# Microcontroller.net
KiCad netlist of a schematic drawn in Altium Designer
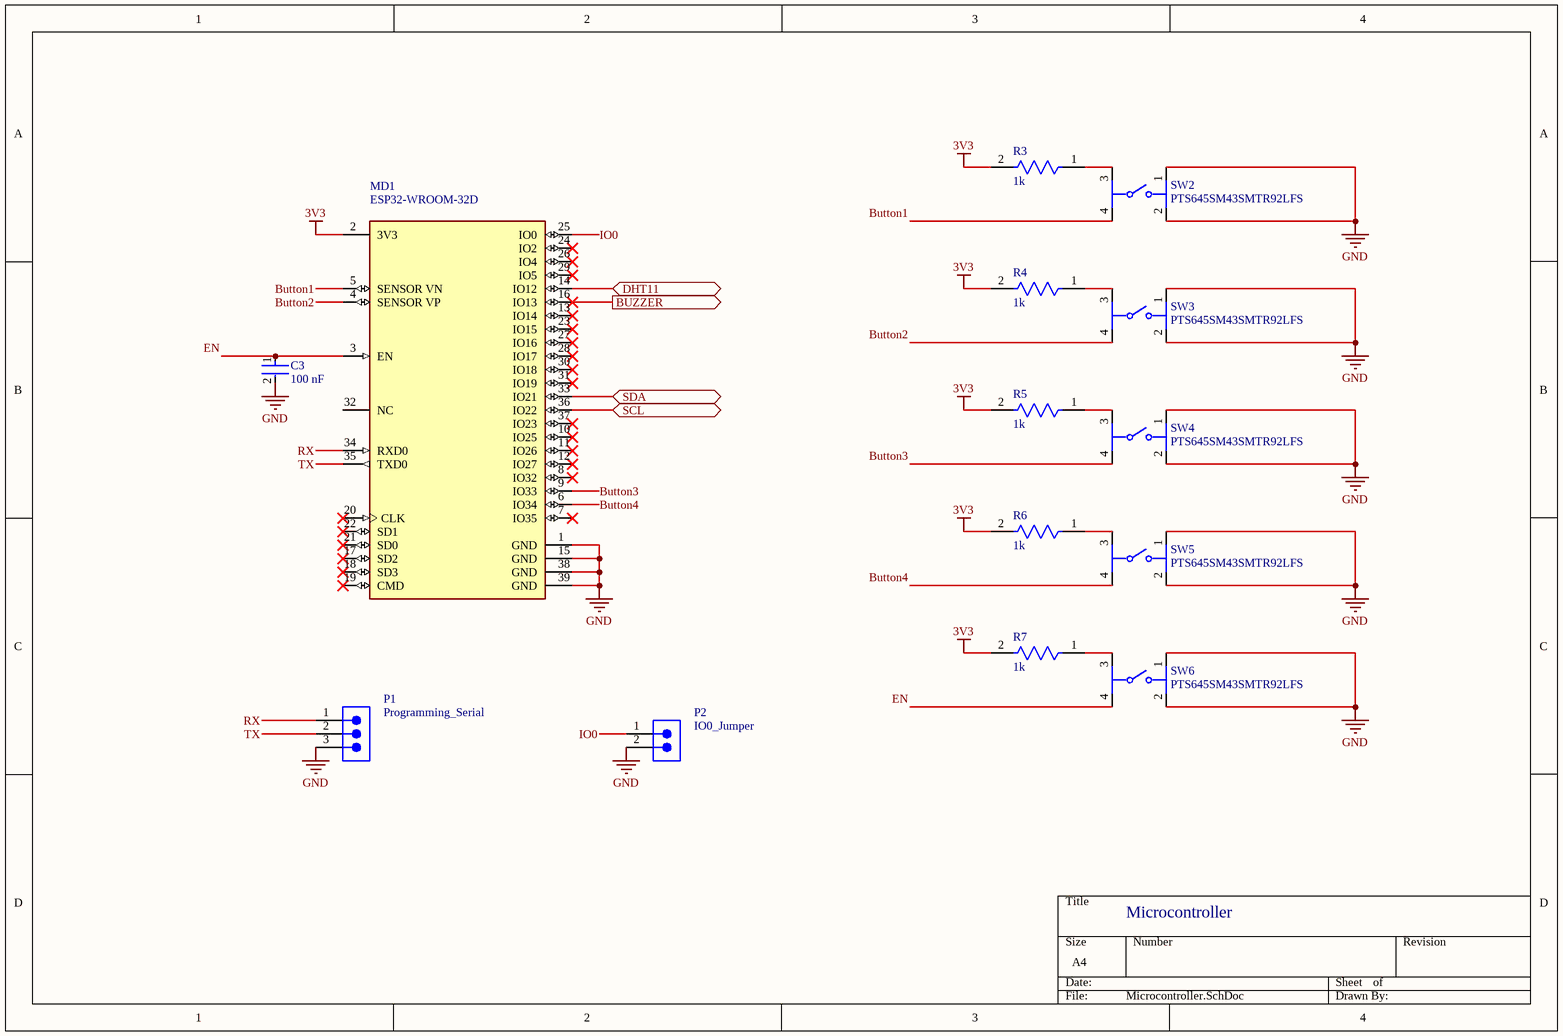
[diagram p0: Microcontroller.SchDoc]

(export (version "E")
  (design (tool "Eeschema 10.0.6"))
  (components
    (comp (ref "C3")
      (value "100 nF")
      (footprint "FP-CC1206-1_25-MFG")
      (description "CAP CER 0.1UF 50V X7R 1206")
      (fields
        (field (name "OCTOPART") "https://octopart.com/cc1206krx7r9bb104-yageo-39467816")
        (field (name "TOLERANCE") "0.1")
      )
      (libsource (lib "Altium Content Vault") (part "11868f565c42a9108669ba33697ecf6"))
    )
    (comp (ref "MD1")
      (value "ESP32-WROOM-32D")
      (footprint "FP-ESP32-WROOM-32D-MFG")
      (description "WIFI MODULE 32MBITS SPI FLASH")
      (fields
        (field (name "OCTOPART") "https://octopart.com/esp32-wroom-32d-espressif+systems-91040050")
        (field (name "MANUFACTURER") "Espressif Systems")
      )
      (libsource (lib "Altium Content Vault") (part "a031a76f8c27026a7a7f4657ff233a3"))
    )
    (comp (ref "P1")
      (value "Programming_Serial")
      (footprint "61900311121")
      (libsource (lib "Altium Content Vault") (part "Header_Male_1R_03P"))
    )
    (comp (ref "P2")
      (value "IO0_Jumper")
      (footprint "61300211121")
      (libsource (lib "Altium Content Vault") (part "Header_Male_1R_02P"))
    )
    (comp (ref "R3")
      (value "1k")
      (footprint "FP-CRCW1206-e3-MFG")
      (description "RES Thick Film, 1.2kΩ, 1%, 0.25W, 100ppm/°C, 1206")
      (fields (field (name "TOLERANCE") "1%"))
      (libsource (lib "Altium Content Vault") (part "1029c3af85768c4190bb7ad29bc67b5"))
    )
    (comp (ref "R4")
      (value "1k")
      (footprint "FP-CRCW1206-e3-MFG")
      (description "RES Thick Film, 1.2kΩ, 1%, 0.25W, 100ppm/°C, 1206")
      (fields (field (name "TOLERANCE") "1%"))
      (libsource (lib "Altium Content Vault") (part "1029c3af85768c4190bb7ad29bc67b5"))
    )
    (comp (ref "R5")
      (value "1k")
      (footprint "FP-CRCW1206-e3-MFG")
      (description "RES Thick Film, 1.2kΩ, 1%, 0.25W, 100ppm/°C, 1206")
      (fields (field (name "TOLERANCE") "1%"))
      (libsource (lib "Altium Content Vault") (part "1029c3af85768c4190bb7ad29bc67b5"))
    )
    (comp (ref "R6")
      (value "1k")
      (footprint "FP-CRCW1206-e3-MFG")
      (description "RES Thick Film, 1.2kΩ, 1%, 0.25W, 100ppm/°C, 1206")
      (fields (field (name "TOLERANCE") "1%"))
      (libsource (lib "Altium Content Vault") (part "1029c3af85768c4190bb7ad29bc67b5"))
    )
    (comp (ref "R7")
      (value "1k")
      (footprint "FP-CRCW1206-e3-MFG")
      (description "RES Thick Film, 1.2kΩ, 1%, 0.25W, 100ppm/°C, 1206")
      (fields (field (name "TOLERANCE") "1%"))
      (libsource (lib "Altium Content Vault") (part "1029c3af85768c4190bb7ad29bc67b5"))
    )
    (comp (ref "SW2")
      (value "PTS645SM43SMTR92LFS")
      (footprint "FP-PTS645SM43SMTR92LFS-MFG")
      (description "SWITCH TACTILE SPST-NO 0.05A 12V")
      (libsource (lib "Altium Content Vault") (part "1adf0dd01260c80cf25a44bfd6b99ba"))
    )
    (comp (ref "SW3")
      (value "PTS645SM43SMTR92LFS")
      (footprint "FP-PTS645SM43SMTR92LFS-MFG")
      (description "SWITCH TACTILE SPST-NO 0.05A 12V")
      (libsource (lib "Altium Content Vault") (part "1adf0dd01260c80cf25a44bfd6b99ba"))
    )
    (comp (ref "SW4")
      (value "PTS645SM43SMTR92LFS")
      (footprint "FP-PTS645SM43SMTR92LFS-MFG")
      (description "SWITCH TACTILE SPST-NO 0.05A 12V")
      (libsource (lib "Altium Content Vault") (part "1adf0dd01260c80cf25a44bfd6b99ba"))
    )
    (comp (ref "SW5")
      (value "PTS645SM43SMTR92LFS")
      (footprint "FP-PTS645SM43SMTR92LFS-MFG")
      (description "SWITCH TACTILE SPST-NO 0.05A 12V")
      (libsource (lib "Altium Content Vault") (part "1adf0dd01260c80cf25a44bfd6b99ba"))
    )
    (comp (ref "SW6")
      (value "PTS645SM43SMTR92LFS")
      (footprint "FP-PTS645SM43SMTR92LFS-MFG")
      (description "SWITCH TACTILE SPST-NO 0.05A 12V")
      (libsource (lib "Altium Content Vault") (part "1adf0dd01260c80cf25a44bfd6b99ba"))
    )
  )
  (nets
    (net (code "1") (name "/BUZZER") (class "Default")
      (node (ref "MD1") (pin "16") (pinfunction "IO13_16") (pintype "bidirectional+no_connect"))
    )
    (net (code "2") (name "/Button1") (class "Default")
      (node (ref "MD1") (pin "5") (pinfunction "SENSOR_VN_5") (pintype "bidirectional"))
      (node (ref "SW2") (pin "4") (pinfunction "4_4") (pintype "passive"))
    )
    (net (code "3") (name "/Button2") (class "Default")
      (node (ref "MD1") (pin "4") (pinfunction "SENSOR_VP_4") (pintype "bidirectional"))
      (node (ref "SW3") (pin "4") (pinfunction "4_4") (pintype "passive"))
    )
    (net (code "4") (name "/Button3") (class "Default")
      (node (ref "MD1") (pin "9") (pinfunction "IO33_9") (pintype "bidirectional"))
      (node (ref "SW4") (pin "4") (pinfunction "4_4") (pintype "passive"))
    )
    (net (code "5") (name "/Button4") (class "Default")
      (node (ref "MD1") (pin "6") (pinfunction "IO34_6") (pintype "bidirectional"))
      (node (ref "SW5") (pin "4") (pinfunction "4_4") (pintype "passive"))
    )
    (net (code "6") (name "/DHT11") (class "Default")
      (node (ref "MD1") (pin "14") (pinfunction "IO12_14") (pintype "bidirectional"))
    )
    (net (code "7") (name "/EN") (class "Default")
      (node (ref "C3") (pin "1") (pinfunction "1_1") (pintype "passive"))
      (node (ref "MD1") (pin "3") (pinfunction "EN_3") (pintype "input"))
      (node (ref "SW6") (pin "4") (pinfunction "4_4") (pintype "passive"))
    )
    (net (code "8") (name "/IO0") (class "Default")
      (node (ref "MD1") (pin "25") (pinfunction "IO0_25") (pintype "bidirectional"))
      (node (ref "P2") (pin "1") (pinfunction "1_1") (pintype "passive"))
    )
    (net (code "9") (name "/RX") (class "Default")
      (node (ref "MD1") (pin "34") (pinfunction "RXD0_34") (pintype "input"))
      (node (ref "P1") (pin "1") (pinfunction "1_1") (pintype "passive"))
    )
    (net (code "10") (name "/SCL") (class "Default")
      (node (ref "MD1") (pin "36") (pinfunction "IO22_36") (pintype "bidirectional"))
    )
    (net (code "11") (name "/SDA") (class "Default")
      (node (ref "MD1") (pin "33") (pinfunction "IO21_33") (pintype "bidirectional"))
    )
    (net (code "12") (name "/TX") (class "Default")
      (node (ref "MD1") (pin "35") (pinfunction "TXD0_35") (pintype "output"))
      (node (ref "P1") (pin "2") (pinfunction "2_2") (pintype "passive"))
    )
    (net (code "13") (name "3V3") (class "Default")
      (node (ref "MD1") (pin "2") (pinfunction "3V3_2") (pintype "power_in"))
      (node (ref "R3") (pin "2") (pinfunction "2_2") (pintype "passive"))
      (node (ref "R4") (pin "2") (pinfunction "2_2") (pintype "passive"))
      (node (ref "R5") (pin "2") (pinfunction "2_2") (pintype "passive"))
      (node (ref "R6") (pin "2") (pinfunction "2_2") (pintype "passive"))
      (node (ref "R7") (pin "2") (pinfunction "2_2") (pintype "passive"))
    )
    (net (code "14") (name "GND") (class "Default")
      (node (ref "C3") (pin "2") (pinfunction "2_2") (pintype "passive"))
      (node (ref "MD1") (pin "1") (pinfunction "GND_1") (pintype "power_in"))
      (node (ref "MD1") (pin "15") (pinfunction "GND_15") (pintype "power_in"))
      (node (ref "MD1") (pin "38") (pinfunction "GND_38") (pintype "power_in"))
      (node (ref "MD1") (pin "39") (pinfunction "GND_39") (pintype "power_in"))
      (node (ref "P1") (pin "3") (pinfunction "3_3") (pintype "passive"))
      (node (ref "P2") (pin "2") (pinfunction "2_2") (pintype "passive"))
      (node (ref "SW2") (pin "1") (pinfunction "1_1") (pintype "passive"))
      (node (ref "SW2") (pin "2") (pinfunction "2_2") (pintype "passive"))
      (node (ref "SW3") (pin "1") (pinfunction "1_1") (pintype "passive"))
      (node (ref "SW3") (pin "2") (pinfunction "2_2") (pintype "passive"))
      (node (ref "SW4") (pin "1") (pinfunction "1_1") (pintype "passive"))
      (node (ref "SW4") (pin "2") (pinfunction "2_2") (pintype "passive"))
      (node (ref "SW5") (pin "1") (pinfunction "1_1") (pintype "passive"))
      (node (ref "SW5") (pin "2") (pinfunction "2_2") (pintype "passive"))
      (node (ref "SW6") (pin "1") (pinfunction "1_1") (pintype "passive"))
      (node (ref "SW6") (pin "2") (pinfunction "2_2") (pintype "passive"))
    )
    (net (code "15") (name "Net-(R3-Pad1)") (class "Default")
      (node (ref "R3") (pin "1") (pinfunction "1_1") (pintype "passive"))
      (node (ref "SW2") (pin "3") (pinfunction "3_3") (pintype "passive"))
    )
    (net (code "16") (name "Net-(R4-Pad1)") (class "Default")
      (node (ref "R4") (pin "1") (pinfunction "1_1") (pintype "passive"))
      (node (ref "SW3") (pin "3") (pinfunction "3_3") (pintype "passive"))
    )
    (net (code "17") (name "Net-(R5-Pad1)") (class "Default")
      (node (ref "R5") (pin "1") (pinfunction "1_1") (pintype "passive"))
      (node (ref "SW4") (pin "3") (pinfunction "3_3") (pintype "passive"))
    )
    (net (code "18") (name "Net-(R6-Pad1)") (class "Default")
      (node (ref "R6") (pin "1") (pinfunction "1_1") (pintype "passive"))
      (node (ref "SW5") (pin "3") (pinfunction "3_3") (pintype "passive"))
    )
    (net (code "19") (name "Net-(R7-Pad1)") (class "Default")
      (node (ref "R7") (pin "1") (pinfunction "1_1") (pintype "passive"))
      (node (ref "SW6") (pin "3") (pinfunction "3_3") (pintype "passive"))
    )
    (net (code "20") (name "unconnected-(MD1-CLK-Pad20)") (class "Default")
      (node (ref "MD1") (pin "20") (pinfunction "CLK_20") (pintype "input+no_connect"))
    )
    (net (code "21") (name "unconnected-(MD1-CMD-Pad19)") (class "Default")
      (node (ref "MD1") (pin "19") (pinfunction "CMD_19") (pintype "bidirectional+no_connect"))
    )
    (net (code "22") (name "unconnected-(MD1-IO2-Pad24)") (class "Default")
      (node (ref "MD1") (pin "24") (pinfunction "IO2_24") (pintype "bidirectional+no_connect"))
    )
    (net (code "23") (name "unconnected-(MD1-IO4-Pad26)") (class "Default")
      (node (ref "MD1") (pin "26") (pinfunction "IO4_26") (pintype "bidirectional+no_connect"))
    )
    (net (code "24") (name "unconnected-(MD1-IO5-Pad29)") (class "Default")
      (node (ref "MD1") (pin "29") (pinfunction "IO5_29") (pintype "bidirectional+no_connect"))
    )
    (net (code "25") (name "unconnected-(MD1-IO14-Pad13)") (class "Default")
      (node (ref "MD1") (pin "13") (pinfunction "IO14_13") (pintype "bidirectional+no_connect"))
    )
    (net (code "26") (name "unconnected-(MD1-IO15-Pad23)") (class "Default")
      (node (ref "MD1") (pin "23") (pinfunction "IO15_23") (pintype "bidirectional+no_connect"))
    )
    (net (code "27") (name "unconnected-(MD1-IO16-Pad27)") (class "Default")
      (node (ref "MD1") (pin "27") (pinfunction "IO16_27") (pintype "bidirectional+no_connect"))
    )
    (net (code "28") (name "unconnected-(MD1-IO17-Pad28)") (class "Default")
      (node (ref "MD1") (pin "28") (pinfunction "IO17_28") (pintype "bidirectional+no_connect"))
    )
    (net (code "29") (name "unconnected-(MD1-IO18-Pad30)") (class "Default")
      (node (ref "MD1") (pin "30") (pinfunction "IO18_30") (pintype "bidirectional+no_connect"))
    )
    (net (code "30") (name "unconnected-(MD1-IO19-Pad31)") (class "Default")
      (node (ref "MD1") (pin "31") (pinfunction "IO19_31") (pintype "bidirectional+no_connect"))
    )
    (net (code "31") (name "unconnected-(MD1-IO23-Pad37)") (class "Default")
      (node (ref "MD1") (pin "37") (pinfunction "IO23_37") (pintype "bidirectional+no_connect"))
    )
    (net (code "32") (name "unconnected-(MD1-IO25-Pad10)") (class "Default")
      (node (ref "MD1") (pin "10") (pinfunction "IO25_10") (pintype "bidirectional+no_connect"))
    )
    (net (code "33") (name "unconnected-(MD1-IO26-Pad11)") (class "Default")
      (node (ref "MD1") (pin "11") (pinfunction "IO26_11") (pintype "bidirectional+no_connect"))
    )
    (net (code "34") (name "unconnected-(MD1-IO27-Pad12)") (class "Default")
      (node (ref "MD1") (pin "12") (pinfunction "IO27_12") (pintype "bidirectional+no_connect"))
    )
    (net (code "35") (name "unconnected-(MD1-IO32-Pad8)") (class "Default")
      (node (ref "MD1") (pin "8") (pinfunction "IO32_8") (pintype "bidirectional+no_connect"))
    )
    (net (code "36") (name "unconnected-(MD1-IO35-Pad7)") (class "Default")
      (node (ref "MD1") (pin "7") (pinfunction "IO35_7") (pintype "bidirectional+no_connect"))
    )
    (net (code "37") (name "unconnected-(MD1-NC-Pad32)") (class "Default")
      (node (ref "MD1") (pin "32") (pinfunction "NC_32") (pintype "passive"))
    )
    (net (code "38") (name "unconnected-(MD1-SD0-Pad21)") (class "Default")
      (node (ref "MD1") (pin "21") (pinfunction "SD0_21") (pintype "bidirectional+no_connect"))
    )
    (net (code "39") (name "unconnected-(MD1-SD1-Pad22)") (class "Default")
      (node (ref "MD1") (pin "22") (pinfunction "SD1_22") (pintype "bidirectional+no_connect"))
    )
    (net (code "40") (name "unconnected-(MD1-SD2-Pad17)") (class "Default")
      (node (ref "MD1") (pin "17") (pinfunction "SD2_17") (pintype "bidirectional+no_connect"))
    )
    (net (code "41") (name "unconnected-(MD1-SD3-Pad18)") (class "Default")
      (node (ref "MD1") (pin "18") (pinfunction "SD3_18") (pintype "bidirectional+no_connect"))
    )
  )
)
